# Microcontroller.net
KiCad netlist of a schematic drawn in Altium Designer
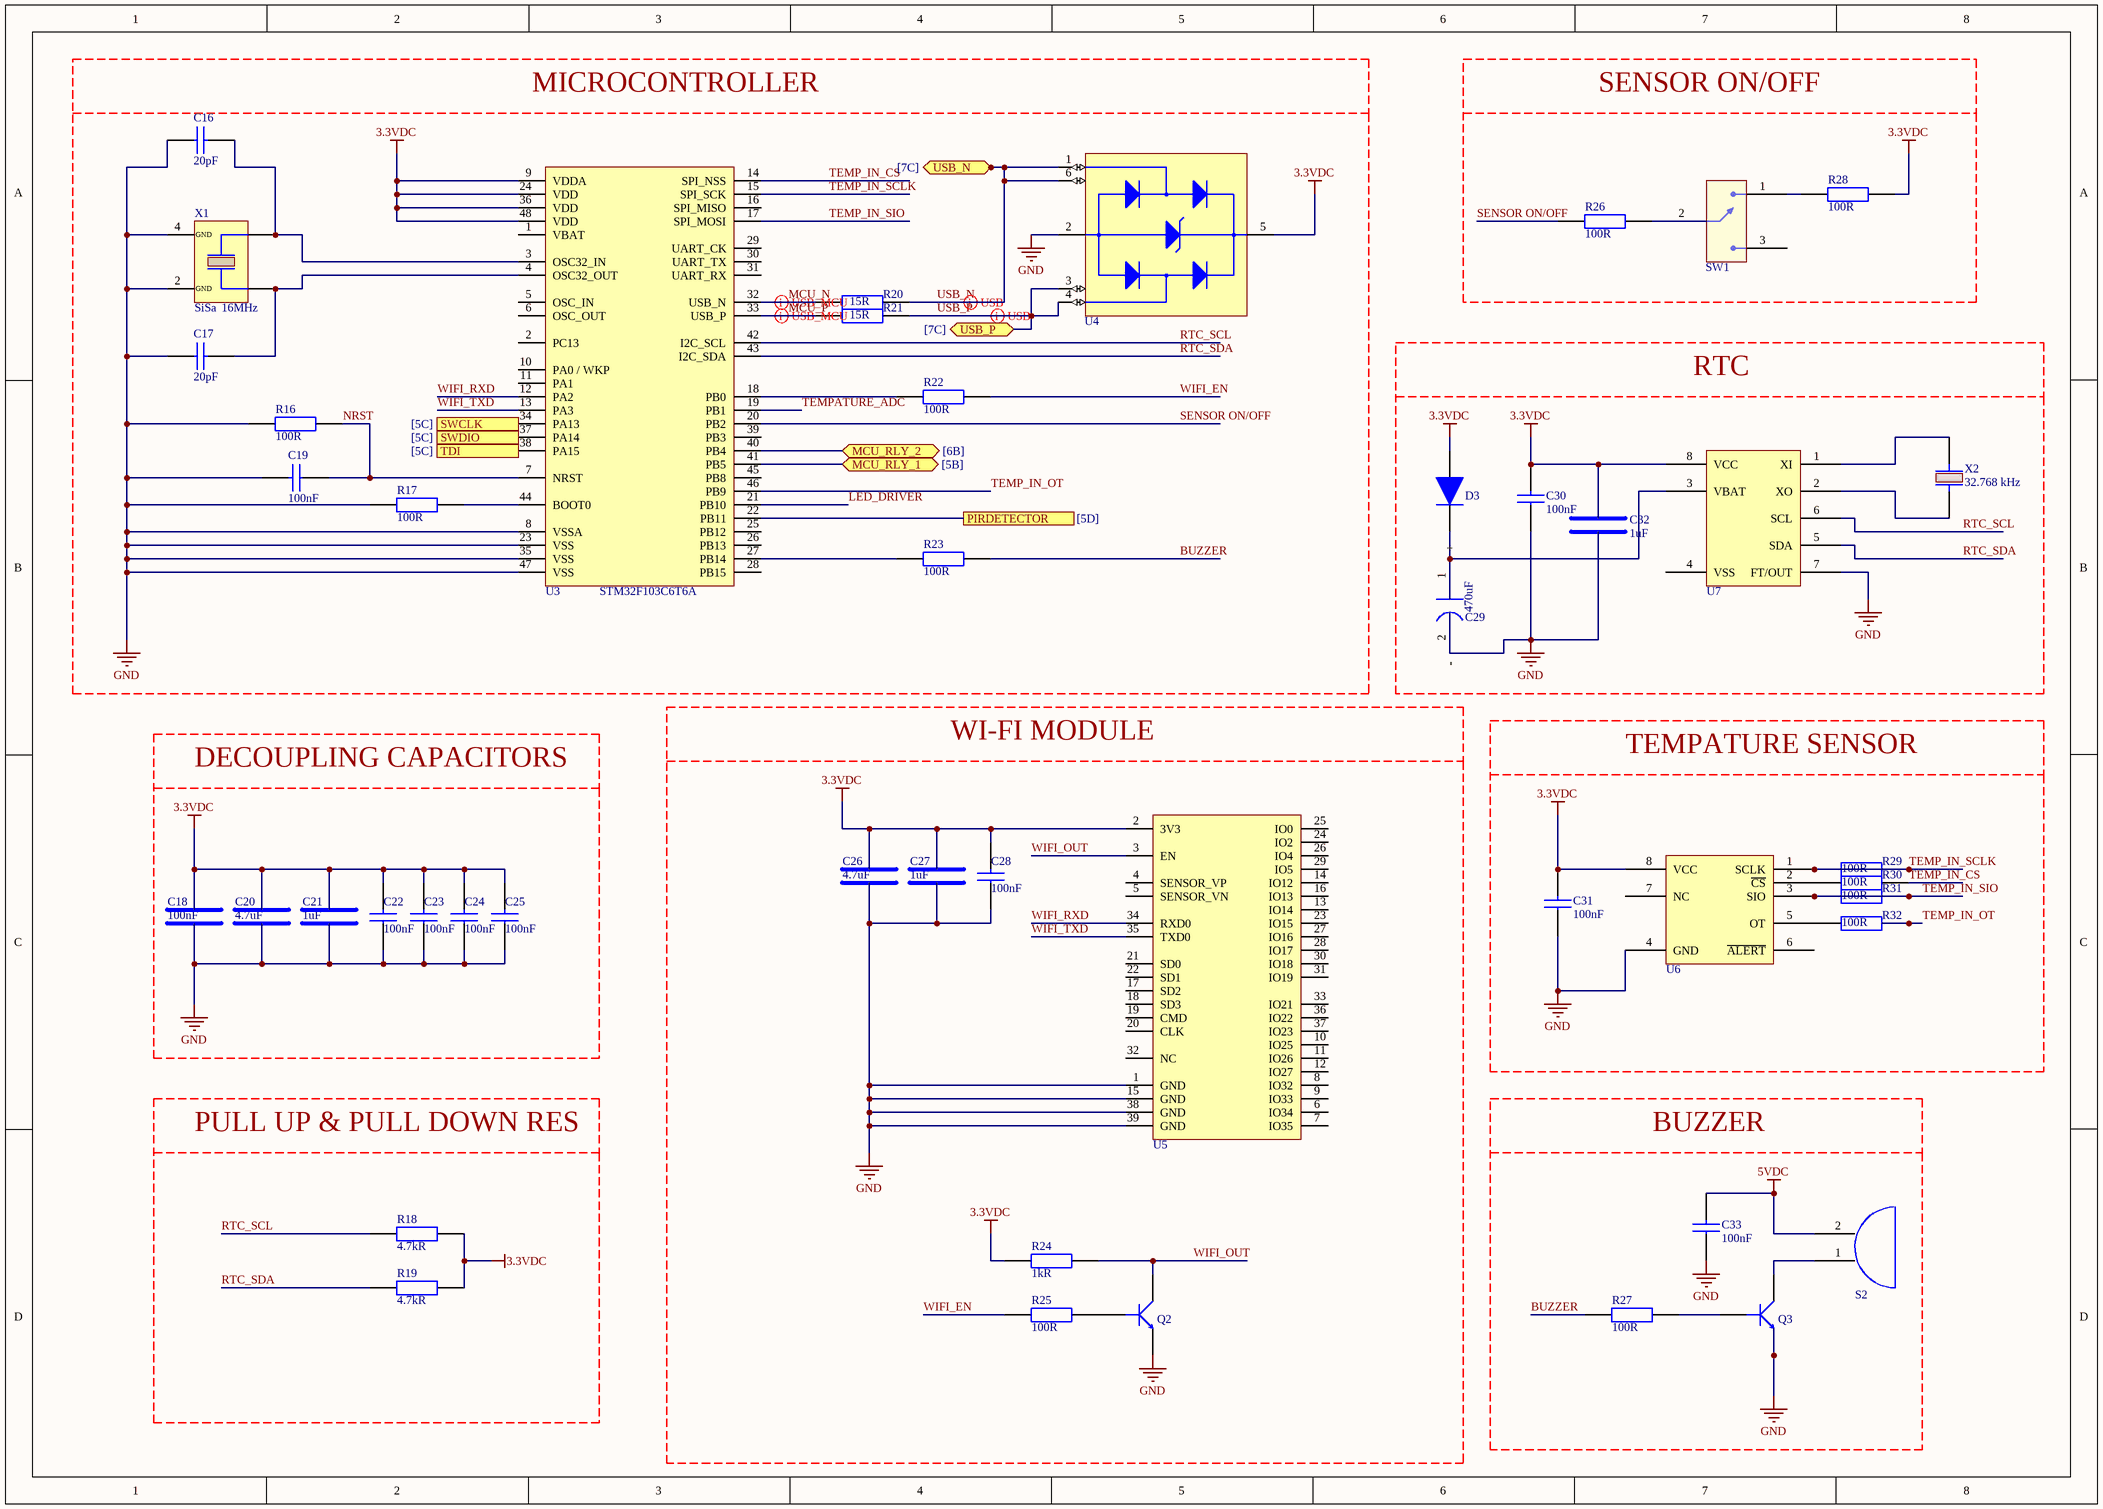
[diagram p0: Microcontroller.SchDoc]

(export (version "E")
  (design (tool "Eeschema 10.0.6"))
  (components
    (comp (ref "C16")
      (value "CL10C200JB8NNNC")
      (footprint "CAP_0603")
      (description "CAP CER 20pF %5 0603 SMD")
      (fields
        (field (name "MANUFACTURER") "Samsung")
        (field (name "TOLERANCE") "5%")
        (field (name "CAPACITANCE") "20pF")
        (field (name "DESIGNED BY") "BERK")
      )
      (libsource (lib "Integrated_Library1") (part "CAP CER 20pF 0603"))
    )
    (comp (ref "C17")
      (value "CL10C200JB8NNNC")
      (footprint "CAP_0603")
      (description "CAP CER 20pF %5 0603 SMD")
      (fields
        (field (name "MANUFACTURER") "Samsung")
        (field (name "TOLERANCE") "5%")
        (field (name "CAPACITANCE") "20pF")
        (field (name "DESIGNED BY") "BERK")
      )
      (libsource (lib "Integrated_Library1") (part "CAP CER 20pF 0603"))
    )
    (comp (ref "C18")
      (value "100nF")
      (footprint "CAP_0603")
      (fields
        (field (name "MANUFACTURER") "KEMET")
        (field (name "MANUFACTURER PART NUMBER") "C0603C104K5RACTU")
      )
      (libsource (lib "Integrated_Library1") (part "C0603C104K5RACTU"))
    )
    (comp (ref "C19")
      (value "C0603C104K5RACTU")
      (footprint "CAP_0603")
      (description "CAP CER 100nF %10 0603 SMD")
      (fields
        (field (name "MANUFACTURER") "KEMET")
        (field (name "TOLERANCE") "10%")
        (field (name "CAPACITANCE") "100nF")
        (field (name "DESIGNED BY") "BERK")
      )
      (libsource (lib "Integrated_Library1") (part "CAP CER 100nF 0603"))
    )
    (comp (ref "C20")
      (value "4.7uF")
      (footprint "CAP_0805")
      (fields
        (field (name "MANUFACTURER") "Samsung")
        (field (name "MANUFACTURER PART NUMBER") "CL21A475KAQNNNE")
      )
      (libsource (lib "Integrated_Library1") (part "CAP CER 4.7uF 0805"))
    )
    (comp (ref "C21")
      (value "1uF")
      (footprint "CAP_0805")
      (fields
        (field (name "MANUFACTURER") "Samsung")
        (field (name "MANUFACTURER PART NUMBER") "CL21B105KBFNNNE")
      )
      (libsource (lib "Integrated_Library1") (part "CAP CER 1uF"))
    )
    (comp (ref "C22")
      (value "C0603C104K5RACTU")
      (footprint "CAP_0603")
      (description "CAP CER 100nF %10 0603 SMD")
      (fields
        (field (name "MANUFACTURER") "KEMET")
        (field (name "TOLERANCE") "10%")
        (field (name "CAPACITANCE") "100nF")
        (field (name "DESIGNED BY") "BERK")
      )
      (libsource (lib "Integrated_Library1") (part "CAP CER 100nF 0603"))
    )
    (comp (ref "C23")
      (value "C0603C104K5RACTU")
      (footprint "CAP_0603")
      (description "CAP CER 100nF %10 0603 SMD")
      (fields
        (field (name "MANUFACTURER") "KEMET")
        (field (name "TOLERANCE") "10%")
        (field (name "CAPACITANCE") "100nF")
        (field (name "DESIGNED BY") "BERK")
      )
      (libsource (lib "Integrated_Library1") (part "CAP CER 100nF 0603"))
    )
    (comp (ref "C24")
      (value "C0603C104K5RACTU")
      (footprint "CAP_0603")
      (description "CAP CER 100nF %10 0603 SMD")
      (fields
        (field (name "MANUFACTURER") "KEMET")
        (field (name "TOLERANCE") "10%")
        (field (name "CAPACITANCE") "100nF")
        (field (name "DESIGNED BY") "BERK")
      )
      (libsource (lib "Integrated_Library1") (part "CAP CER 100nF 0603"))
    )
    (comp (ref "C25")
      (value "C0603C104K5RACTU")
      (footprint "CAP_0603")
      (description "CAP CER 100nF %10 0603 SMD")
      (fields
        (field (name "MANUFACTURER") "KEMET")
        (field (name "TOLERANCE") "10%")
        (field (name "CAPACITANCE") "100nF")
        (field (name "DESIGNED BY") "BERK")
      )
      (libsource (lib "Integrated_Library1") (part "CAP CER 100nF 0603"))
    )
    (comp (ref "C26")
      (value "4.7uF")
      (footprint "CAP_0805")
      (fields
        (field (name "MANUFACTURER") "Samsung")
        (field (name "MANUFACTURER PART NUMBER") "CL21A475KAQNNNE")
      )
      (libsource (lib "Integrated_Library1") (part "CAP CER 4.7uF 0805"))
    )
    (comp (ref "C27")
      (value "1uF")
      (footprint "CAP_0805")
      (fields
        (field (name "MANUFACTURER") "Samsung")
        (field (name "MANUFACTURER PART NUMBER") "CL21B105KBFNNNE")
      )
      (libsource (lib "Integrated_Library1") (part "CAP CER 1uF"))
    )
    (comp (ref "C28")
      (value "C0603C104K5RACTU")
      (footprint "CAP_0603")
      (description "CAP CER 100nF %10 0603 SMD")
      (fields
        (field (name "MANUFACTURER") "KEMET")
        (field (name "TOLERANCE") "10%")
        (field (name "CAPACITANCE") "100nF")
        (field (name "DESIGNED BY") "BERK")
      )
      (libsource (lib "Integrated_Library1") (part "CAP CER 100nF 0603"))
    )
    (comp (ref "C29")
      (value "470uF")
      (footprint "ESH477M050AH4AA")
      (fields
        (field (name "MANUFACTURER") "KEMET")
        (field (name "MANUFACTURER PART NUMBER") "ESH477M050AH4AA")
      )
      (libsource (lib "Integrated_Library1") (part "ESH477M050AH4AA"))
    )
    (comp (ref "C30")
      (value "C0603C104K5RACTU")
      (footprint "CAP_0603")
      (description "CAP CER 100nF %10 0603 SMD")
      (fields
        (field (name "MANUFACTURER") "KEMET")
        (field (name "TOLERANCE") "10%")
        (field (name "CAPACITANCE") "100nF")
        (field (name "DESIGNED BY") "BERK")
      )
      (libsource (lib "Integrated_Library1") (part "CAP CER 100nF 0603"))
    )
    (comp (ref "C31")
      (value "C0603C104K5RACTU")
      (footprint "CAP_0603")
      (description "CAP CER 100nF %10 0603 SMD")
      (fields
        (field (name "MANUFACTURER") "KEMET")
        (field (name "TOLERANCE") "10%")
        (field (name "CAPACITANCE") "100nF")
        (field (name "DESIGNED BY") "BERK")
      )
      (libsource (lib "Integrated_Library1") (part "CAP CER 100nF 0603"))
    )
    (comp (ref "C32")
      (value "1uF")
      (footprint "CAP_0805")
      (fields
        (field (name "MANUFACTURER") "Samsung")
        (field (name "MANUFACTURER PART NUMBER") "CL21B105KBFNNNE")
      )
      (libsource (lib "Integrated_Library1") (part "CAP CER 1uF"))
    )
    (comp (ref "C33")
      (value "C0603C104K5RACTU")
      (footprint "CAP_0603")
      (description "CAP CER 100nF %10 0603 SMD")
      (fields
        (field (name "MANUFACTURER") "KEMET")
        (field (name "TOLERANCE") "10%")
        (field (name "CAPACITANCE") "100nF")
        (field (name "DESIGNED BY") "BERK")
      )
      (libsource (lib "Integrated_Library1") (part "CAP CER 100nF 0603"))
    )
    (comp (ref "D3")
      (value "1N4148WS")
      (footprint "SOD323F")
      (description "Diode, Single, 75 V, 150 mA, 1 V, 4 ns")
      (fields (field (name "MANUFACTURER") "ON Semiconductor / Fairchild"))
      (libsource (lib "Integrated_Library1") (part "1N4148WS"))
    )
    (comp (ref "Q2")
      (value "MMBT3904-7-F")
      (footprint "SOT-23F")
      (description "Transistor General Purpose BJT NPN 40 Volt 0.2A Automotive 3-Pin SOT-23")
      (fields (field (name "MANUFACTURER") "Diodes Zetex"))
      (libsource (lib "Integrated_Library1") (part "MMBT3904-7-F"))
    )
    (comp (ref "Q3")
      (value "MMBT3904-7-F")
      (footprint "SOT-23F")
      (description "Transistor General Purpose BJT NPN 40 Volt 0.2A Automotive 3-Pin SOT-23")
      (fields (field (name "MANUFACTURER") "Diodes Zetex"))
      (libsource (lib "Integrated_Library1") (part "MMBT3904-7-F"))
    )
    (comp (ref "R16")
      (value "RC0603JR-07100RL")
      (footprint "RES_0603 - duplicate")
      (description "RES 100 %5 OHM 0603 SMD")
      (fields
        (field (name "MANUFACTURER") "Yageo")
        (field (name "TOLERANCE") "5%")
        (field (name "RESISTANCE") "100R")
        (field (name "DESIGNED BY") "BERK")
      )
      (libsource (lib "Integrated_Library1") (part "RES 100 OHM 0603"))
    )
    (comp (ref "R17")
      (value "RC0603JR-07100RL")
      (footprint "RES_0603 - duplicate")
      (description "RES 100 %5 OHM 0603 SMD")
      (fields
        (field (name "MANUFACTURER") "Yageo")
        (field (name "TOLERANCE") "5%")
        (field (name "RESISTANCE") "100R")
        (field (name "DESIGNED BY") "BERK")
      )
      (libsource (lib "Integrated_Library1") (part "RES 100 OHM 0603"))
    )
    (comp (ref "R18")
      (value "RC0603JR-074K7L")
      (footprint "RES_0603 - duplicate")
      (description "RES 4K7 %5 OHM 0603 SMD")
      (fields
        (field (name "MANUFACTURER") "Yageo")
        (field (name "TOLERANCE") "5%")
        (field (name "RESISTANCE") "4.7kR")
        (field (name "DESIGNED BY") "BERK")
      )
      (libsource (lib "Integrated_Library1") (part "RES 4K7 OHM 0603"))
    )
    (comp (ref "R19")
      (value "RC0603JR-074K7L")
      (footprint "RES_0603 - duplicate")
      (description "RES 4K7 %5 OHM 0603 SMD")
      (fields
        (field (name "MANUFACTURER") "Yageo")
        (field (name "TOLERANCE") "5%")
        (field (name "RESISTANCE") "4.7kR")
        (field (name "DESIGNED BY") "BERK")
      )
      (libsource (lib "Integrated_Library1") (part "RES 4K7 OHM 0603"))
    )
    (comp (ref "R20")
      (value "RC0603JR-0715RL")
      (footprint "RES_0603 - duplicate")
      (description "RES 15 %5 OHM 0603 SMD")
      (fields
        (field (name "MANUFACTURER") "Yageo")
        (field (name "TOLERANCE") "5%")
        (field (name "RESISTANCE") "15R")
        (field (name "DESIGNED BY") "BERK")
      )
      (libsource (lib "Integrated_Library1") (part "RES 15 OHM 0603"))
    )
    (comp (ref "R21")
      (value "RC0603JR-0715RL")
      (footprint "RES_0603 - duplicate")
      (description "RES 15 %5 OHM 0603 SMD")
      (fields
        (field (name "MANUFACTURER") "Yageo")
        (field (name "TOLERANCE") "5%")
        (field (name "RESISTANCE") "15R")
        (field (name "DESIGNED BY") "BERK")
      )
      (libsource (lib "Integrated_Library1") (part "RES 15 OHM 0603"))
    )
    (comp (ref "R22")
      (value "RC0603JR-07100RL")
      (footprint "RES_0603 - duplicate")
      (description "RES 100 %5 OHM 0603 SMD")
      (fields
        (field (name "MANUFACTURER") "Yageo")
        (field (name "TOLERANCE") "5%")
        (field (name "RESISTANCE") "100R")
        (field (name "DESIGNED BY") "BERK")
      )
      (libsource (lib "Integrated_Library1") (part "RES 100 OHM 0603"))
    )
    (comp (ref "R23")
      (value "RC0603JR-07100RL")
      (footprint "RES_0603 - duplicate")
      (description "RES 100 %5 OHM 0603 SMD")
      (fields
        (field (name "MANUFACTURER") "Yageo")
        (field (name "TOLERANCE") "5%")
        (field (name "RESISTANCE") "100R")
        (field (name "DESIGNED BY") "BERK")
      )
      (libsource (lib "Integrated_Library1") (part "RES 100 OHM 0603"))
    )
    (comp (ref "R24")
      (value "RC0603FR-0710KL")
      (footprint "RES_0603 - duplicate")
      (description "RES 1K %1 OHM 0603 SMD")
      (fields
        (field (name "MANUFACTURER") "Yageo")
        (field (name "MANUFACTURER PART NUMBER") "RC0603JR-071KL")
        (field (name "RESISTANCE") "1kR")
        (field (name "DESIGNED BY") "BERK")
      )
      (libsource (lib "Integrated_Library1") (part "RES 1K OHM 0603"))
    )
    (comp (ref "R25")
      (value "RC0603JR-07100RL")
      (footprint "RES_0603 - duplicate")
      (description "RES 100 %5 OHM 0603 SMD")
      (fields
        (field (name "MANUFACTURER") "Yageo")
        (field (name "TOLERANCE") "5%")
        (field (name "RESISTANCE") "100R")
        (field (name "DESIGNED BY") "BERK")
      )
      (libsource (lib "Integrated_Library1") (part "RES 100 OHM 0603"))
    )
    (comp (ref "R26")
      (value "RC0603JR-07100RL")
      (footprint "RES_0603 - duplicate")
      (description "RES 100 %5 OHM 0603 SMD")
      (fields
        (field (name "MANUFACTURER") "Yageo")
        (field (name "TOLERANCE") "5%")
        (field (name "RESISTANCE") "100R")
        (field (name "DESIGNED BY") "BERK")
      )
      (libsource (lib "Integrated_Library1") (part "RES 100 OHM 0603"))
    )
    (comp (ref "R27")
      (value "RC0603JR-07100RL")
      (footprint "RES_0603 - duplicate")
      (description "RES 100 %5 OHM 0603 SMD")
      (fields
        (field (name "MANUFACTURER") "Yageo")
        (field (name "TOLERANCE") "5%")
        (field (name "RESISTANCE") "100R")
        (field (name "DESIGNED BY") "BERK")
      )
      (libsource (lib "Integrated_Library1") (part "RES 100 OHM 0603"))
    )
    (comp (ref "R28")
      (value "RC0603JR-07100RL")
      (footprint "RES_0603 - duplicate")
      (description "RES 100 %5 OHM 0603 SMD")
      (fields
        (field (name "MANUFACTURER") "Yageo")
        (field (name "TOLERANCE") "5%")
        (field (name "RESISTANCE") "100R")
        (field (name "DESIGNED BY") "BERK")
      )
      (libsource (lib "Integrated_Library1") (part "RES 100 OHM 0603"))
    )
    (comp (ref "R29")
      (value "RC0603JR-07100RL")
      (footprint "RES_0603 - duplicate")
      (description "RES 100 %5 OHM 0603 SMD")
      (fields
        (field (name "MANUFACTURER") "Yageo")
        (field (name "TOLERANCE") "5%")
        (field (name "RESISTANCE") "100R")
        (field (name "DESIGNED BY") "BERK")
      )
      (libsource (lib "Integrated_Library1") (part "RES 100 OHM 0603"))
    )
    (comp (ref "R30")
      (value "RC0603JR-07100RL")
      (footprint "RES_0603 - duplicate")
      (description "RES 100 %5 OHM 0603 SMD")
      (fields
        (field (name "MANUFACTURER") "Yageo")
        (field (name "TOLERANCE") "5%")
        (field (name "RESISTANCE") "100R")
        (field (name "DESIGNED BY") "BERK")
      )
      (libsource (lib "Integrated_Library1") (part "RES 100 OHM 0603"))
    )
    (comp (ref "R31")
      (value "RC0603JR-07100RL")
      (footprint "RES_0603 - duplicate")
      (description "RES 100 %5 OHM 0603 SMD")
      (fields
        (field (name "MANUFACTURER") "Yageo")
        (field (name "TOLERANCE") "5%")
        (field (name "RESISTANCE") "100R")
        (field (name "DESIGNED BY") "BERK")
      )
      (libsource (lib "Integrated_Library1") (part "RES 100 OHM 0603"))
    )
    (comp (ref "R32")
      (value "RC0603JR-07100RL")
      (footprint "RES_0603 - duplicate")
      (description "RES 100 %5 OHM 0603 SMD")
      (fields
        (field (name "MANUFACTURER") "Yageo")
        (field (name "TOLERANCE") "5%")
        (field (name "RESISTANCE") "100R")
        (field (name "DESIGNED BY") "BERK")
      )
      (libsource (lib "Integrated_Library1") (part "RES 100 OHM 0603"))
    )
    (comp (ref "S2")
      (value "CMI-9605IC-0580T")
      (footprint "CMI-9605IC-0580T")
      (description "9.6 mm, 5 Vdc, 80 dB, Through Hole, Driving Circuit, Magnetic Audio Indicator Buzzer")
      (fields (field (name "MANUFACTURER") "Same Sky") (field (name "DESIGNED BY") "sisa"))
      (libsource (lib "Integrated_Library1") (part "CMI-9605IC-0580T"))
    )
    (comp (ref "SW1")
      (value "EG1215AA")
      (footprint "EG1215AA")
      (description "Slide Switch")
      (fields (field (name "MANUFACTURER") "E-Switch") (field (name "DESIGNED BY") "sisa"))
      (libsource (lib "Integrated_Library1") (part "EG1215AA"))
    )
    (comp (ref "U3")
      (value "STM32F103C6T6A")
      (footprint "LFQP-48")
      (description "RISC Microcontroller, 32-Bit, FLASH, CORTEX-M3 CPU, 72MHz, CMOS, PQFP48")
      (fields (field (name "MANUFACTURER") "STMicroelectronics") (field (name "DESIGNED BY") "SiSa"))
      (libsource (lib "Integrated_Library1") (part "STM32F103C6T6A"))
    )
    (comp (ref "U4")
      (value "USBLC6-2SC6")
      (footprint "SOT23-6L")
      (description "TVS DIODE 5.25V 17V SOT23-6")
      (fields (field (name "MANUFACTURER") "STMicroelectronics") (field (name "DESIGNED BY") "BERK"))
      (libsource (lib "Integrated_Library1") (part "USB PROTECTION"))
    )
    (comp (ref "U5")
      (value "EPS32-WROOM-32E (4MB)")
      (footprint "ESP32-32 NW")
      (description "Rx Txrx Mod Wifi Trace Ant SMD")
      (fields
        (field (name "MANUFACTURER") "Espressif Systems")
        (field (name "MANUFACTURER PART NUMBER") "ESP32-WROOM-32E-H4")
        (field (name "DESIGNED BY") "SiSa")
      )
      (libsource (lib "Integrated_Library1") (part "EPS32-WROOM-32E (4MB)"))
    )
    (comp (ref "U6")
      (value "MAX6662MSA")
      (footprint "SOIC8")
      (description "Serial Switch/Digital Sensor, 12 Bit(s), 2.50Cel, BICMOS, Rectangular, 8 Pin, Surface Mount")
      (fields (field (name "MANUFACTURER") "Maxim") (field (name "MANUFACTURER PART NUMBER") "MAX6662MSA+"))
      (libsource (lib "Integrated_Library1") (part "MAX6662MSA"))
    )
    (comp (ref "U7")
      (value "M41T00")
      (footprint "SOIC8")
      (description "Real Time Clock, Volatile, 0 Timer(s), CMOS, PDSO8")
      (fields
        (field (name "MANUFACTURER") "STMicroelectronics")
        (field (name "MANUFACTURER PART NUMBER") "M41T00SM6F")
        (field (name "DESIGNED BY") "SiSa")
      )
      (libsource (lib "Integrated_Library1") (part "M41T00"))
    )
    (comp (ref "X1")
      (value "ECS-160-20-30B-TR")
      (footprint "ECS")
      (description "CRYSTAL 16.0000MHZ 20PF SMD")
      (fields
        (field (name "MANUFACTURER") "ECS International")
        (field (name "TOLERANCE") "50ppm")
        (field (name ",") "SiSa")
        (field (name "FREQUENCY") "16MHz")
      )
      (libsource (lib "Integrated_Library1") (part "CRYSTAL 16MHz"))
    )
    (comp (ref "X2")
      (value "ABS05-32.768KHZ-T")
      (footprint "ABS05")
      (description "Crystal, 32.768 kHz, SMD, 1.6mm x 1mm, 12.5 pF, 20 ppm, ABS05 Series")
      (fields
        (field (name "MANUFACTURER") "Abracon")
        (field (name "TOLERANCE") "20ppm")
        (field (name "OPERATING FREQUENCY") "32.768 kHz")
      )
      (libsource (lib "Integrated_Library1") (part "CRYSTAL 32768kHZ"))
    )
  )
  (nets
    (net (code "1") (name "/BUZZER") (class "Default")
      (node (ref "R23") (pin "2") (pinfunction "2_2") (pintype "passive"))
      (node (ref "R27") (pin "1") (pinfunction "1_1") (pintype "passive"))
    )
    (net (code "2") (name "/LED_DRIVER") (class "Default")
      (node (ref "U3") (pin "21") (pinfunction "PB10_21") (pintype "passive"))
    )
    (net (code "3") (name "/MCU_N") (class "Default")
      (node (ref "R20") (pin "1") (pinfunction "1_1") (pintype "passive"))
      (node (ref "U3") (pin "32") (pinfunction "USB_N_32") (pintype "passive"))
    )
    (net (code "4") (name "/MCU_P") (class "Default")
      (node (ref "R21") (pin "1") (pinfunction "1_1") (pintype "passive"))
      (node (ref "U3") (pin "33") (pinfunction "USB_P_33") (pintype "passive"))
    )
    (net (code "5") (name "/MCU_RLY_1") (class "Default")
      (node (ref "U3") (pin "41") (pinfunction "PB5_41") (pintype "passive"))
    )
    (net (code "6") (name "/MCU_RLY_2") (class "Default")
      (node (ref "U3") (pin "40") (pinfunction "PB4_40") (pintype "passive"))
    )
    (net (code "7") (name "/NRST") (class "Default")
      (node (ref "C19") (pin "1") (pinfunction "1_1") (pintype "passive"))
      (node (ref "R16") (pin "2") (pinfunction "2_2") (pintype "passive"))
      (node (ref "U3") (pin "7") (pinfunction "NRST_7") (pintype "passive"))
    )
    (net (code "8") (name "/PIRDETECTOR") (class "Default")
      (node (ref "U3") (pin "22") (pinfunction "PB11_22") (pintype "passive"))
    )
    (net (code "9") (name "/RTC_SCL") (class "Default")
      (node (ref "R18") (pin "1") (pinfunction "1_1") (pintype "passive"))
      (node (ref "U3") (pin "42") (pinfunction "I2C_SCL_42") (pintype "passive"))
      (node (ref "U7") (pin "6") (pinfunction "SCL_6") (pintype "passive"))
    )
    (net (code "10") (name "/RTC_SDA") (class "Default")
      (node (ref "R19") (pin "1") (pinfunction "1_1") (pintype "passive"))
      (node (ref "U3") (pin "43") (pinfunction "I2C_SDA_43") (pintype "passive"))
      (node (ref "U7") (pin "5") (pinfunction "SDA_5") (pintype "passive"))
    )
    (net (code "11") (name "/SENSOR ON{slash}OFF") (class "Default")
      (node (ref "R26") (pin "1") (pinfunction "1_1") (pintype "passive"))
      (node (ref "U3") (pin "20") (pinfunction "PB2_20") (pintype "passive"))
    )
    (net (code "12") (name "/SWCLK") (class "Default")
      (node (ref "U3") (pin "34") (pinfunction "PA13_34") (pintype "passive"))
    )
    (net (code "13") (name "/SWDIO") (class "Default")
      (node (ref "U3") (pin "37") (pinfunction "PA14_37") (pintype "passive"))
    )
    (net (code "14") (name "/TDI") (class "Default")
      (node (ref "U3") (pin "38") (pinfunction "PA15_38") (pintype "passive"))
    )
    (net (code "15") (name "/TEMPATURE_ADC") (class "Default")
      (node (ref "U3") (pin "19") (pinfunction "PB1_19") (pintype "passive"))
    )
    (net (code "16") (name "/TEMP_IN_CS") (class "Default")
      (node (ref "R30") (pin "2") (pinfunction "2_2") (pintype "passive"))
      (node (ref "U3") (pin "14") (pinfunction "SPI_NSS_14") (pintype "passive"))
    )
    (net (code "17") (name "/TEMP_IN_OT") (class "Default")
      (node (ref "R32") (pin "2") (pinfunction "2_2") (pintype "passive"))
      (node (ref "U3") (pin "46") (pinfunction "PB9_46") (pintype "passive"))
    )
    (net (code "18") (name "/TEMP_IN_SCLK") (class "Default")
      (node (ref "R29") (pin "1") (pinfunction "1_1") (pintype "passive"))
      (node (ref "R29") (pin "2") (pinfunction "2_2") (pintype "passive"))
      (node (ref "U3") (pin "15") (pinfunction "SPI_SCK_15") (pintype "passive"))
      (node (ref "U6") (pin "1") (pinfunction "SCLK_1") (pintype "passive"))
    )
    (net (code "19") (name "/TEMP_IN_SIO") (class "Default")
      (node (ref "R31") (pin "1") (pinfunction "1_1") (pintype "passive"))
      (node (ref "R31") (pin "2") (pinfunction "2_2") (pintype "passive"))
      (node (ref "U3") (pin "17") (pinfunction "SPI_MOSI_17") (pintype "passive"))
      (node (ref "U6") (pin "3") (pinfunction "SIO_3") (pintype "passive"))
    )
    (net (code "20") (name "/USB_N") (class "Default")
      (node (ref "R20") (pin "2") (pinfunction "2_2") (pintype "passive"))
      (node (ref "U4") (pin "1") (pinfunction "I/O1_1") (pintype "bidirectional"))
      (node (ref "U4") (pin "6") (pinfunction "I/O1_6") (pintype "bidirectional"))
    )
    (net (code "21") (name "/USB_P") (class "Default")
      (node (ref "R21") (pin "2") (pinfunction "2_2") (pintype "passive"))
      (node (ref "U4") (pin "3") (pinfunction "I/O2_3") (pintype "bidirectional"))
      (node (ref "U4") (pin "4") (pinfunction "I/O2_4") (pintype "bidirectional"))
    )
    (net (code "22") (name "/WIFI_EN") (class "Default")
      (node (ref "R22") (pin "2") (pinfunction "2_2") (pintype "passive"))
      (node (ref "R25") (pin "1") (pinfunction "1_1") (pintype "passive"))
    )
    (net (code "23") (name "/WIFI_OUT") (class "Default")
      (node (ref "Q2") (pin "3") (pinfunction "C_3") (pintype "power_in"))
      (node (ref "R24") (pin "2") (pinfunction "2_2") (pintype "passive"))
      (node (ref "U5") (pin "3") (pinfunction "EN_3") (pintype "passive"))
    )
    (net (code "24") (name "/WIFI_RXD") (class "Default")
      (node (ref "U3") (pin "12") (pinfunction "PA2_12") (pintype "passive"))
      (node (ref "U5") (pin "34") (pinfunction "RXD0_34") (pintype "passive"))
    )
    (net (code "25") (name "/WIFI_TXD") (class "Default")
      (node (ref "U3") (pin "13") (pinfunction "PA3_13") (pintype "passive"))
      (node (ref "U5") (pin "35") (pinfunction "TXD0_35") (pintype "passive"))
    )
    (net (code "26") (name "3.3VDC") (class "Default")
      (node (ref "C18") (pin "1") (pinfunction "1_1") (pintype "passive"))
      (node (ref "C20") (pin "1") (pinfunction "1_1") (pintype "passive"))
      (node (ref "C21") (pin "1") (pinfunction "1_1") (pintype "passive"))
      (node (ref "C22") (pin "2") (pinfunction "2_2") (pintype "passive"))
      (node (ref "C23") (pin "2") (pinfunction "2_2") (pintype "passive"))
      (node (ref "C24") (pin "2") (pinfunction "2_2") (pintype "passive"))
      (node (ref "C25") (pin "2") (pinfunction "2_2") (pintype "passive"))
      (node (ref "C26") (pin "1") (pinfunction "1_1") (pintype "passive"))
      (node (ref "C27") (pin "1") (pinfunction "1_1") (pintype "passive"))
      (node (ref "C28") (pin "2") (pinfunction "2_2") (pintype "passive"))
      (node (ref "C30") (pin "2") (pinfunction "2_2") (pintype "passive"))
      (node (ref "C31") (pin "2") (pinfunction "2_2") (pintype "passive"))
      (node (ref "C32") (pin "1") (pinfunction "1_1") (pintype "passive"))
      (node (ref "D3") (pin "2") (pinfunction "2_2") (pintype "power_in"))
      (node (ref "R18") (pin "2") (pinfunction "2_2") (pintype "passive"))
      (node (ref "R19") (pin "2") (pinfunction "2_2") (pintype "passive"))
      (node (ref "R24") (pin "1") (pinfunction "1_1") (pintype "passive"))
      (node (ref "R28") (pin "2") (pinfunction "2_2") (pintype "passive"))
      (node (ref "U3") (pin "24") (pinfunction "VDD_24") (pintype "passive"))
      (node (ref "U3") (pin "36") (pinfunction "VDD_36") (pintype "passive"))
      (node (ref "U3") (pin "48") (pinfunction "VDD_48") (pintype "passive"))
      (node (ref "U3") (pin "9") (pinfunction "VDDA_9") (pintype "passive"))
      (node (ref "U4") (pin "5") (pinfunction "VBUS_5") (pintype "power_in"))
      (node (ref "U5") (pin "2") (pinfunction "3V3_2") (pintype "passive"))
      (node (ref "U6") (pin "8") (pinfunction "VCC_8") (pintype "passive"))
      (node (ref "U7") (pin "8") (pinfunction "VCC_8") (pintype "passive"))
    )
    (net (code "27") (name "5VDC") (class "Default")
      (node (ref "C33") (pin "2") (pinfunction "2_2") (pintype "passive"))
      (node (ref "S2") (pin "2") (pinfunction "2_2") (pintype "passive"))
    )
    (net (code "28") (name "GND") (class "Default")
      (node (ref "C16") (pin "1") (pinfunction "1_1") (pintype "passive"))
      (node (ref "C17") (pin "1") (pinfunction "1_1") (pintype "passive"))
      (node (ref "C18") (pin "2") (pinfunction "2_2") (pintype "passive"))
      (node (ref "C19") (pin "2") (pinfunction "2_2") (pintype "passive"))
      (node (ref "C20") (pin "2") (pinfunction "2_2") (pintype "passive"))
      (node (ref "C21") (pin "2") (pinfunction "2_2") (pintype "passive"))
      (node (ref "C22") (pin "1") (pinfunction "1_1") (pintype "passive"))
      (node (ref "C23") (pin "1") (pinfunction "1_1") (pintype "passive"))
      (node (ref "C24") (pin "1") (pinfunction "1_1") (pintype "passive"))
      (node (ref "C25") (pin "1") (pinfunction "1_1") (pintype "passive"))
      (node (ref "C26") (pin "2") (pinfunction "2_2") (pintype "passive"))
      (node (ref "C27") (pin "2") (pinfunction "2_2") (pintype "passive"))
      (node (ref "C28") (pin "1") (pinfunction "1_1") (pintype "passive"))
      (node (ref "C29") (pin "2") (pinfunction "-_2") (pintype "passive"))
      (node (ref "C30") (pin "1") (pinfunction "1_1") (pintype "passive"))
      (node (ref "C31") (pin "1") (pinfunction "1_1") (pintype "passive"))
      (node (ref "C32") (pin "2") (pinfunction "2_2") (pintype "passive"))
      (node (ref "C33") (pin "1") (pinfunction "1_1") (pintype "passive"))
      (node (ref "Q2") (pin "2") (pinfunction "E_2") (pintype "power_in"))
      (node (ref "Q3") (pin "2") (pinfunction "E_2") (pintype "power_in"))
      (node (ref "R16") (pin "1") (pinfunction "1_1") (pintype "passive"))
      (node (ref "R17") (pin "1") (pinfunction "1_1") (pintype "passive"))
      (node (ref "U3") (pin "23") (pinfunction "VSS_23") (pintype "passive"))
      (node (ref "U3") (pin "35") (pinfunction "VSS_35") (pintype "passive"))
      (node (ref "U3") (pin "47") (pinfunction "VSS_47") (pintype "passive"))
      (node (ref "U3") (pin "8") (pinfunction "VSSA_8") (pintype "passive"))
      (node (ref "U4") (pin "2") (pinfunction "GND_2") (pintype "power_in"))
      (node (ref "U5") (pin "1") (pinfunction "GND_1") (pintype "passive"))
      (node (ref "U5") (pin "15") (pinfunction "GND_15") (pintype "passive"))
      (node (ref "U5") (pin "38") (pinfunction "GND_38") (pintype "passive"))
      (node (ref "U5") (pin "39") (pinfunction "GND_39") (pintype "passive"))
      (node (ref "U6") (pin "4") (pinfunction "GND_4") (pintype "passive"))
      (node (ref "U7") (pin "7") (pinfunction "FT/OUT_7") (pintype "passive"))
      (node (ref "X1") (pin "2") (pinfunction "GND_2") (pintype "passive"))
      (node (ref "X1") (pin "4") (pinfunction "GND_4") (pintype "passive"))
    )
    (net (code "29") (name "Net-(C29-+)") (class "Default")
      (node (ref "C29") (pin "1") (pinfunction "+_1") (pintype "passive"))
      (node (ref "D3") (pin "1") (pinfunction "1_1") (pintype "power_in"))
      (node (ref "U7") (pin "3") (pinfunction "VBAT_3") (pintype "passive"))
    )
    (net (code "30") (name "Net-(Q2-B)") (class "Default")
      (node (ref "Q2") (pin "1") (pinfunction "B_1") (pintype "power_in"))
      (node (ref "R25") (pin "2") (pinfunction "2_2") (pintype "passive"))
    )
    (net (code "31") (name "Net-(Q3-B)") (class "Default")
      (node (ref "Q3") (pin "1") (pinfunction "B_1") (pintype "power_in"))
      (node (ref "R27") (pin "2") (pinfunction "2_2") (pintype "passive"))
    )
    (net (code "32") (name "Net-(Q3-C)") (class "Default")
      (node (ref "Q3") (pin "3") (pinfunction "C_3") (pintype "power_in"))
      (node (ref "S2") (pin "1") (pinfunction "1_1") (pintype "passive"))
    )
    (net (code "33") (name "Net-(SW1-6)") (class "Default")
      (node (ref "R26") (pin "2") (pinfunction "2_2") (pintype "passive"))
      (node (ref "SW1") (pin "2") (pinfunction "6_2") (pintype "passive"))
    )
    (net (code "34") (name "Net-(SW1-7)") (class "Default")
      (node (ref "R28") (pin "1") (pinfunction "1_1") (pintype "passive"))
      (node (ref "SW1") (pin "1") (pinfunction "7_1") (pintype "passive"))
    )
    (net (code "35") (name "Net-(U3-BOOT0)") (class "Default")
      (node (ref "R17") (pin "2") (pinfunction "2_2") (pintype "passive"))
      (node (ref "U3") (pin "44") (pinfunction "BOOT0_44") (pintype "passive"))
    )
    (net (code "36") (name "Net-(U3-OSC32_IN)") (class "Default")
      (node (ref "C16") (pin "2") (pinfunction "2_2") (pintype "passive"))
      (node (ref "U3") (pin "3") (pinfunction "OSC32_IN_3") (pintype "passive"))
      (node (ref "X1") (pin "3") (pinfunction "3_3") (pintype "passive"))
    )
    (net (code "37") (name "Net-(U3-OSC32_OUT)") (class "Default")
      (node (ref "C17") (pin "2") (pinfunction "2_2") (pintype "passive"))
      (node (ref "U3") (pin "4") (pinfunction "OSC32_OUT_4") (pintype "passive"))
      (node (ref "X1") (pin "1") (pinfunction "1_1") (pintype "passive"))
    )
    (net (code "38") (name "Net-(U3-PB0)") (class "Default")
      (node (ref "R22") (pin "1") (pinfunction "1_1") (pintype "passive"))
      (node (ref "U3") (pin "18") (pinfunction "PB0_18") (pintype "passive"))
    )
    (net (code "39") (name "Net-(U3-PB14)") (class "Default")
      (node (ref "R23") (pin "1") (pinfunction "1_1") (pintype "passive"))
      (node (ref "U3") (pin "27") (pinfunction "PB14_27") (pintype "passive"))
    )
    (net (code "40") (name "Net-(U6-OT)") (class "Default")
      (node (ref "R32") (pin "1") (pinfunction "1_1") (pintype "passive"))
      (node (ref "U6") (pin "5") (pinfunction "OT_5") (pintype "passive"))
    )
    (net (code "41") (name "Net-(U6-~{CS})") (class "Default")
      (node (ref "R30") (pin "1") (pinfunction "1_1") (pintype "passive"))
      (node (ref "U6") (pin "2") (pinfunction "~{CS}_2") (pintype "passive"))
    )
    (net (code "42") (name "Net-(U7-XI)") (class "Default")
      (node (ref "U7") (pin "1") (pinfunction "XI_1") (pintype "passive"))
      (node (ref "X2") (pin "2") (pinfunction "2_2") (pintype "passive"))
    )
    (net (code "43") (name "Net-(U7-XO)") (class "Default")
      (node (ref "U7") (pin "2") (pinfunction "XO_2") (pintype "passive"))
      (node (ref "X2") (pin "1") (pinfunction "1_1") (pintype "passive"))
    )
    (net (code "44") (name "unconnected-(SW1-8-Pad3)") (class "Default")
      (node (ref "SW1") (pin "3") (pinfunction "8_3") (pintype "passive"))
    )
    (net (code "45") (name "unconnected-(U3-OSC_IN-Pad5)") (class "Default")
      (node (ref "U3") (pin "5") (pinfunction "OSC_IN_5") (pintype "passive"))
    )
    (net (code "46") (name "unconnected-(U3-OSC_OUT-Pad6)") (class "Default")
      (node (ref "U3") (pin "6") (pinfunction "OSC_OUT_6") (pintype "passive"))
    )
    (net (code "47") (name "unconnected-(U3-PA0_{slash}_WKP-Pad10)") (class "Default")
      (node (ref "U3") (pin "10") (pinfunction "PA0_/_WKP_10") (pintype "passive"))
    )
    (net (code "48") (name "unconnected-(U3-PA1-Pad11)") (class "Default")
      (node (ref "U3") (pin "11") (pinfunction "PA1_11") (pintype "passive"))
    )
    (net (code "49") (name "unconnected-(U3-PB3-Pad39)") (class "Default")
      (node (ref "U3") (pin "39") (pinfunction "PB3_39") (pintype "passive"))
    )
    (net (code "50") (name "unconnected-(U3-PB8-Pad45)") (class "Default")
      (node (ref "U3") (pin "45") (pinfunction "PB8_45") (pintype "passive"))
    )
    (net (code "51") (name "unconnected-(U3-PB12-Pad25)") (class "Default")
      (node (ref "U3") (pin "25") (pinfunction "PB12_25") (pintype "passive"))
    )
    (net (code "52") (name "unconnected-(U3-PB13-Pad26)") (class "Default")
      (node (ref "U3") (pin "26") (pinfunction "PB13_26") (pintype "passive"))
    )
    (net (code "53") (name "unconnected-(U3-PB15-Pad28)") (class "Default")
      (node (ref "U3") (pin "28") (pinfunction "PB15_28") (pintype "passive"))
    )
    (net (code "54") (name "unconnected-(U3-PC13-Pad2)") (class "Default")
      (node (ref "U3") (pin "2") (pinfunction "PC13_2") (pintype "passive"))
    )
    (net (code "55") (name "unconnected-(U3-SPI_MISO-Pad16)") (class "Default")
      (node (ref "U3") (pin "16") (pinfunction "SPI_MISO_16") (pintype "passive"))
    )
    (net (code "56") (name "unconnected-(U3-UART_CK-Pad29)") (class "Default")
      (node (ref "U3") (pin "29") (pinfunction "UART_CK_29") (pintype "passive"))
    )
    (net (code "57") (name "unconnected-(U3-UART_RX-Pad31)") (class "Default")
      (node (ref "U3") (pin "31") (pinfunction "UART_RX_31") (pintype "passive"))
    )
    (net (code "58") (name "unconnected-(U3-UART_TX-Pad30)") (class "Default")
      (node (ref "U3") (pin "30") (pinfunction "UART_TX_30") (pintype "passive"))
    )
    (net (code "59") (name "unconnected-(U3-VBAT-Pad1)") (class "Default")
      (node (ref "U3") (pin "1") (pinfunction "VBAT_1") (pintype "passive"))
    )
    (net (code "60") (name "unconnected-(U5-CLK-Pad20)") (class "Default")
      (node (ref "U5") (pin "20") (pinfunction "CLK_20") (pintype "passive"))
    )
    (net (code "61") (name "unconnected-(U5-CMD-Pad19)") (class "Default")
      (node (ref "U5") (pin "19") (pinfunction "CMD_19") (pintype "passive"))
    )
    (net (code "62") (name "unconnected-(U5-IO0-Pad25)") (class "Default")
      (node (ref "U5") (pin "25") (pinfunction "IO0_25") (pintype "passive"))
    )
    (net (code "63") (name "unconnected-(U5-IO2-Pad24)") (class "Default")
      (node (ref "U5") (pin "24") (pinfunction "IO2_24") (pintype "passive"))
    )
    (net (code "64") (name "unconnected-(U5-IO4-Pad26)") (class "Default")
      (node (ref "U5") (pin "26") (pinfunction "IO4_26") (pintype "passive"))
    )
    (net (code "65") (name "unconnected-(U5-IO5-Pad29)") (class "Default")
      (node (ref "U5") (pin "29") (pinfunction "IO5_29") (pintype "passive"))
    )
    (net (code "66") (name "unconnected-(U5-IO12-Pad14)") (class "Default")
      (node (ref "U5") (pin "14") (pinfunction "IO12_14") (pintype "passive"))
    )
    (net (code "67") (name "unconnected-(U5-IO13-Pad16)") (class "Default")
      (node (ref "U5") (pin "16") (pinfunction "IO13_16") (pintype "passive"))
    )
    (net (code "68") (name "unconnected-(U5-IO14-Pad13)") (class "Default")
      (node (ref "U5") (pin "13") (pinfunction "IO14_13") (pintype "passive"))
    )
    (net (code "69") (name "unconnected-(U5-IO15-Pad23)") (class "Default")
      (node (ref "U5") (pin "23") (pinfunction "IO15_23") (pintype "passive"))
    )
    (net (code "70") (name "unconnected-(U5-IO16-Pad27)") (class "Default")
      (node (ref "U5") (pin "27") (pinfunction "IO16_27") (pintype "passive"))
    )
    (net (code "71") (name "unconnected-(U5-IO17-Pad28)") (class "Default")
      (node (ref "U5") (pin "28") (pinfunction "IO17_28") (pintype "passive"))
    )
    (net (code "72") (name "unconnected-(U5-IO18-Pad30)") (class "Default")
      (node (ref "U5") (pin "30") (pinfunction "IO18_30") (pintype "passive"))
    )
    (net (code "73") (name "unconnected-(U5-IO19-Pad31)") (class "Default")
      (node (ref "U5") (pin "31") (pinfunction "IO19_31") (pintype "passive"))
    )
    (net (code "74") (name "unconnected-(U5-IO21-Pad33)") (class "Default")
      (node (ref "U5") (pin "33") (pinfunction "IO21_33") (pintype "passive"))
    )
    (net (code "75") (name "unconnected-(U5-IO22-Pad36)") (class "Default")
      (node (ref "U5") (pin "36") (pinfunction "IO22_36") (pintype "passive"))
    )
    (net (code "76") (name "unconnected-(U5-IO23-Pad37)") (class "Default")
      (node (ref "U5") (pin "37") (pinfunction "IO23_37") (pintype "passive"))
    )
    (net (code "77") (name "unconnected-(U5-IO25-Pad10)") (class "Default")
      (node (ref "U5") (pin "10") (pinfunction "IO25_10") (pintype "passive"))
    )
    (net (code "78") (name "unconnected-(U5-IO26-Pad11)") (class "Default")
      (node (ref "U5") (pin "11") (pinfunction "IO26_11") (pintype "passive"))
    )
    (net (code "79") (name "unconnected-(U5-IO27-Pad12)") (class "Default")
      (node (ref "U5") (pin "12") (pinfunction "IO27_12") (pintype "passive"))
    )
    (net (code "80") (name "unconnected-(U5-IO32-Pad8)") (class "Default")
      (node (ref "U5") (pin "8") (pinfunction "IO32_8") (pintype "passive"))
    )
    (net (code "81") (name "unconnected-(U5-IO33-Pad9)") (class "Default")
      (node (ref "U5") (pin "9") (pinfunction "IO33_9") (pintype "passive"))
    )
    (net (code "82") (name "unconnected-(U5-IO34-Pad6)") (class "Default")
      (node (ref "U5") (pin "6") (pinfunction "IO34_6") (pintype "passive"))
    )
    (net (code "83") (name "unconnected-(U5-IO35-Pad7)") (class "Default")
      (node (ref "U5") (pin "7") (pinfunction "IO35_7") (pintype "passive"))
    )
    (net (code "84") (name "unconnected-(U5-NC-Pad32)") (class "Default")
      (node (ref "U5") (pin "32") (pinfunction "NC_32") (pintype "passive"))
    )
    (net (code "85") (name "unconnected-(U5-SD0-Pad21)") (class "Default")
      (node (ref "U5") (pin "21") (pinfunction "SD0_21") (pintype "passive"))
    )
    (net (code "86") (name "unconnected-(U5-SD1-Pad22)") (class "Default")
      (node (ref "U5") (pin "22") (pinfunction "SD1_22") (pintype "passive"))
    )
    (net (code "87") (name "unconnected-(U5-SD2-Pad17)") (class "Default")
      (node (ref "U5") (pin "17") (pinfunction "SD2_17") (pintype "passive"))
    )
    (net (code "88") (name "unconnected-(U5-SD3-Pad18)") (class "Default")
      (node (ref "U5") (pin "18") (pinfunction "SD3_18") (pintype "passive"))
    )
    (net (code "89") (name "unconnected-(U5-SENSOR_VN-Pad5)") (class "Default")
      (node (ref "U5") (pin "5") (pinfunction "SENSOR_VN_5") (pintype "passive"))
    )
    (net (code "90") (name "unconnected-(U5-SENSOR_VP-Pad4)") (class "Default")
      (node (ref "U5") (pin "4") (pinfunction "SENSOR_VP_4") (pintype "passive"))
    )
    (net (code "91") (name "unconnected-(U6-NC-Pad7)") (class "Default")
      (node (ref "U6") (pin "7") (pinfunction "NC_7") (pintype "passive"))
    )
    (net (code "92") (name "unconnected-(U6-~{ALERT}-Pad6)") (class "Default")
      (node (ref "U6") (pin "6") (pinfunction "~{ALERT}_6") (pintype "passive"))
    )
    (net (code "93") (name "unconnected-(U7-VSS-Pad4)") (class "Default")
      (node (ref "U7") (pin "4") (pinfunction "VSS_4") (pintype "passive"))
    )
  )
)
